# DC-DC_Controller.net
KiCad netlist of a schematic drawn in Altium Designer
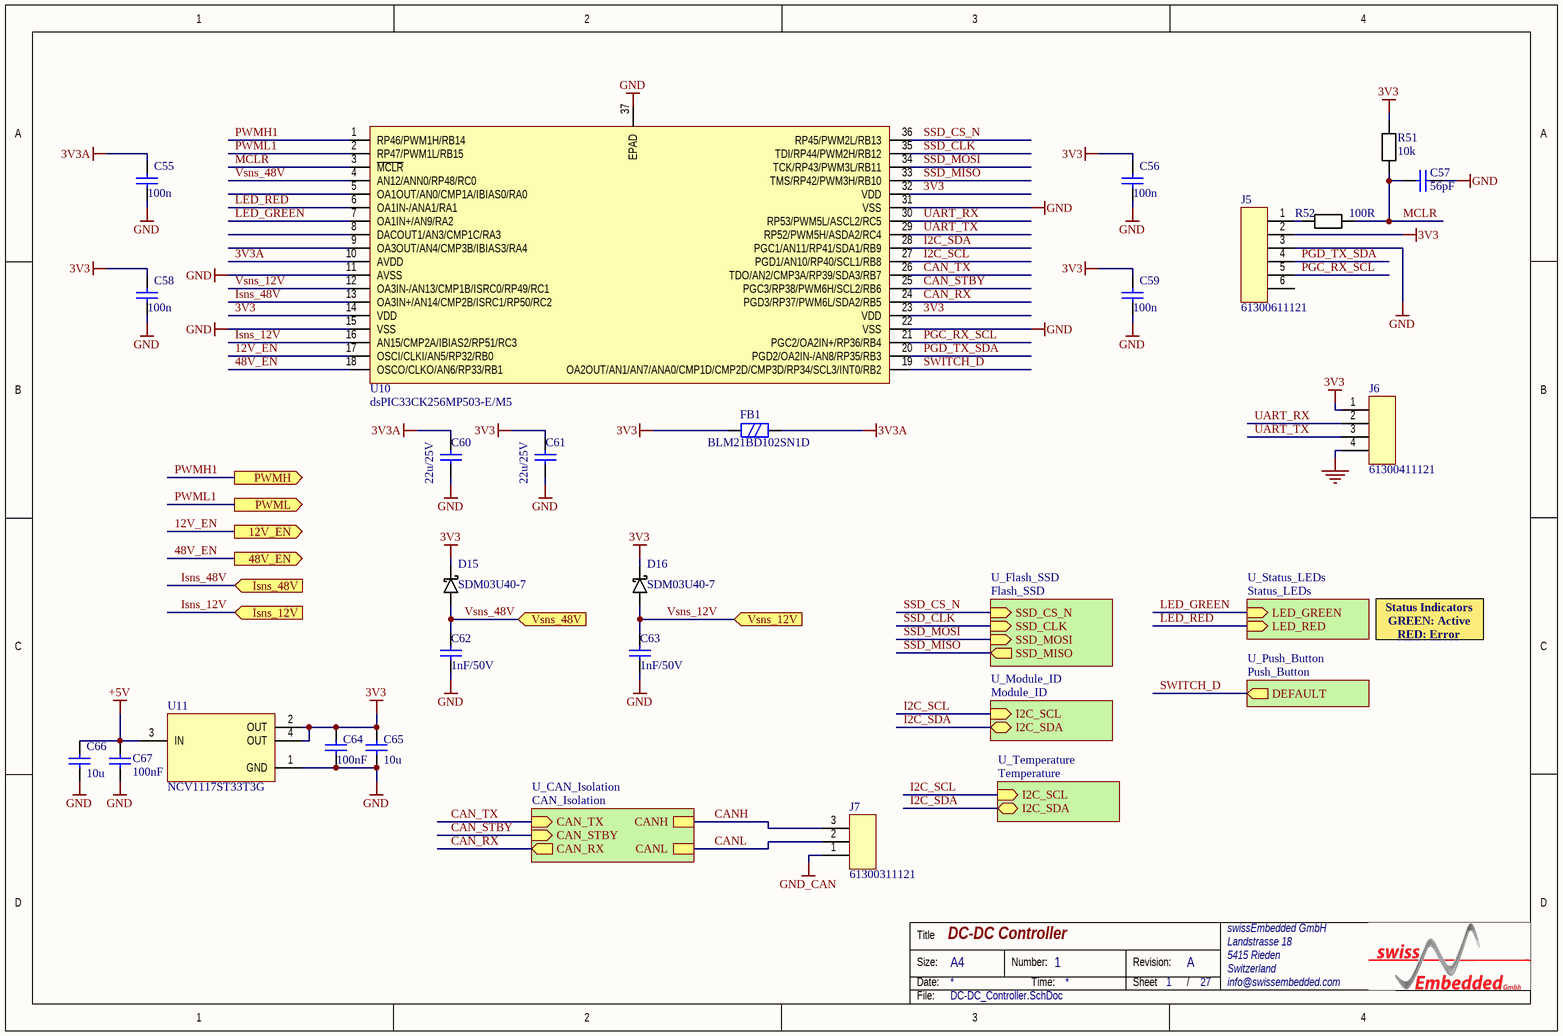
[diagram p0: DC-DC_Controller.SchDoc]

(export (version "E")
  (design (tool "Eeschema 10.0.6"))
  (components
    (comp (ref "C55")
      (value "100n")
      (footprint "C0603")
      (description "100nF ±10% 50V")
      (fields
        (field (name "PART NUMBER") "CAP_YAG_CC0603KRX7R9BB104_X7R")
        (field (name "MANUFACTURER") "Yageo")
      )
      (libsource (lib "Cap_Yag_0603_X7R_50_10%$") (part "CAP_YAG_CC0603KRX7R9BB104_X7R"))
    )
    (comp (ref "C56")
      (value "100n")
      (footprint "C0603")
      (description "100nF ±10% 50V")
      (fields
        (field (name "PART NUMBER") "CAP_YAG_CC0603KRX7R9BB104_X7R")
        (field (name "MANUFACTURER") "Yageo")
      )
      (libsource (lib "Cap_Yag_0603_X7R_50_10%$") (part "CAP_YAG_CC0603KRX7R9BB104_X7R"))
    )
    (comp (ref "C57")
      (value "56pF")
      (footprint "C0603")
      (description "330pF ± 5% 50V")
      (fields
        (field (name "MANUFACTURER") "Yageo")
        (field (name "MANUFACTURER PART NUMBER") "CC0603JRNPO9BN560")
      )
      (libsource (lib "RCL") (part "CAP"))
    )
    (comp (ref "C58")
      (value "100n")
      (footprint "C0603")
      (description "100nF ±10% 50V")
      (fields
        (field (name "PART NUMBER") "CAP_YAG_CC0603KRX7R9BB104_X7R")
        (field (name "MANUFACTURER") "Yageo")
      )
      (libsource (lib "Cap_Yag_0603_X7R_50_10%$") (part "CAP_YAG_CC0603KRX7R9BB104_X7R"))
    )
    (comp (ref "C59")
      (value "100n")
      (footprint "C0603")
      (description "100nF ±10% 50V")
      (fields
        (field (name "PART NUMBER") "CAP_YAG_CC0603KRX7R9BB104_X7R")
        (field (name "MANUFACTURER") "Yageo")
      )
      (libsource (lib "Cap_Yag_0603_X7R_50_10%$") (part "CAP_YAG_CC0603KRX7R9BB104_X7R"))
    )
    (comp (ref "C60")
      (value "22u/25V")
      (footprint "C0805")
      (description "22uF ±10% 25V")
      (fields
        (field (name "MANUFACTURER") "Yageo")
        (field (name "MANUFACTURER PART NUMBER") "CC0805MKX5R8BB226")
      )
      (libsource (lib "RCL") (part "CAP"))
    )
    (comp (ref "C61")
      (value "22u/25V")
      (footprint "C0805")
      (description "22uF ±10% 25V")
      (fields
        (field (name "MANUFACTURER") "Yageo")
        (field (name "MANUFACTURER PART NUMBER") "CC0805MKX5R8BB226")
      )
      (libsource (lib "RCL") (part "CAP"))
    )
    (comp (ref "C62")
      (value "1nF/50V")
      (footprint "C0603")
      (description "1nF ±10% 50V")
      (fields
        (field (name "MANUFACTURER") "Yageo")
        (field (name "MANUFACTURER PART NUMBER") "CC0603KRNPO9BN102")
      )
      (libsource (lib "RCL") (part "CAP"))
    )
    (comp (ref "C63")
      (value "1nF/50V")
      (footprint "C0603")
      (description "1nF ±10% 50V")
      (fields
        (field (name "MANUFACTURER") "Yageo")
        (field (name "MANUFACTURER PART NUMBER") "CC0603KRNPO9BN102")
      )
      (libsource (lib "RCL") (part "CAP"))
    )
    (comp (ref "C64")
      (value "100nF")
      (footprint "C0603")
      (description "100nF ± 10% 50V")
      (fields
        (field (name "MANUFACTURER") "Yageo")
        (field (name "MANUFACTURER PART NUMBER") "CC0603KRX7R9BB104")
      )
      (libsource (lib "Humidity Regulator") (part "100nF ± 10% 50V"))
    )
    (comp (ref "C65")
      (value "10u")
      (footprint "C1206")
      (description "10uF ± 10% 25V")
      (fields
        (field (name "MANUFACTURER") "Yageo")
        (field (name "MANUFACTURER PART NUMBER") "CC1206KKX7R8BB106")
      )
      (libsource (lib "Humidity Regulator") (part "10uF ± 10% 25V"))
    )
    (comp (ref "C66")
      (value "10u")
      (footprint "C1206")
      (description "10uF ± 10% 25V")
      (fields
        (field (name "MANUFACTURER") "Yageo")
        (field (name "MANUFACTURER PART NUMBER") "CC1206KKX7R8BB106")
      )
      (libsource (lib "Humidity Regulator") (part "10uF ± 10% 25V"))
    )
    (comp (ref "C67")
      (value "100nF")
      (footprint "C0603")
      (description "100nF ± 10% 50V")
      (fields
        (field (name "MANUFACTURER") "Yageo")
        (field (name "MANUFACTURER PART NUMBER") "CC0603KRX7R9BB104")
      )
      (libsource (lib "Humidity Regulator") (part "100nF ± 10% 50V"))
    )
    (comp (ref "D15")
      (value "SDM03U40-7")
      (footprint "SOD523")
      (description "Schottky Diodes & Rectifiers 40V 150mW")
      (fields (field (name "MANUFACTURER") "Diodes Incorporated"))
      (libsource (lib "EMDO601_Patch") (part "SDM03U40-7"))
    )
    (comp (ref "D16")
      (value "SDM03U40-7")
      (footprint "SOD523")
      (description "Schottky Diodes & Rectifiers 40V 150mW")
      (fields (field (name "MANUFACTURER") "Diodes Incorporated"))
      (libsource (lib "EMDO601_Patch") (part "SDM03U40-7"))
    )
    (comp (ref "FB1")
      (value "BLM21BD102SN1D")
      (footprint "R0805")
      (description "FERRITE BEAD 1 KOHM 0805 1LN")
      (fields (field (name "MANUFACTURER") "Murata Electronics"))
      (libsource (lib "SchematicLib") (part "SMD_FB"))
    )
    (comp (ref "J5")
      (value "61300611121")
      (footprint "Header-2.54m-6pin")
      (description "6 Pins 2.54mm Pitch Male Connector")
      (fields (field (name "MANUFACTURER") "Wurth Elektronik"))
      (libsource (lib "WirelessCharger") (part "6PinConnector"))
    )
    (comp (ref "J6")
      (value "61300411121")
      (footprint "Header-2.54m-4pin")
      (description "Headers & Wire Housings WR-PHD 2.54mm Hdr 4P Single Str Gold")
      (fields (field (name "MANUFACTURER") "Wurth"))
      (libsource (lib "EMDO601_Patch") (part "61300411121"))
    )
    (comp (ref "J7")
      (value "61300311121")
      (footprint "Header-2.54m-3pin")
      (description "Headers & Wire Housings WR-PHD 2.54mm Hdr 3P Single Str Gold")
      (fields (field (name "MANUFACTURER") "Wurth"))
      (libsource (lib "EMDO601_Patch") (part "61300311121"))
    )
    (comp (ref "R51")
      (value "10k")
      (footprint "R0603")
      (description "0.1W/ 10kohm±1%")
      (fields
        (field (name "MANUFACTURER PART NUMBER") "RC0603FR-0710KL")
        (field (name "MANUFACTURER") "Yageo")
      )
      (libsource (lib "RCL") (part "RES"))
    )
    (comp (ref "R52")
      (value "100R")
      (footprint "R0603")
      (description "0.1W/ 100 ohm±1%")
      (fields
        (field (name "MANUFACTURER PART NUMBER") "RC0603FR-07100RL")
        (field (name "MANUFACTURER") "Yageo")
      )
      (libsource (lib "RCL") (part "RES"))
    )
    (comp (ref "U10")
      (value "dsPIC33CK256MP503-E/M5")
      (footprint "UQFN-36")
      (fields
        (field (name "MANUFACTURER") "Microchip Technology")
        (field (name "ALTERNATIVE PART NUMBER") "dsPIC33CK128MP203-I/M5")
      )
      (libsource (lib "EMDO601_Patch") (part "dsPIC33CK256MP503-E/M5"))
    )
    (comp (ref "U11")
      (value "NCV1117ST33T3G")
      (footprint "SOT223-3")
      (description "LDO Voltage Regulators 3.3V 1.0A Automotive")
      (fields (field (name "MANUFACTURER") "onsemi"))
      (libsource (lib "Humidity Regulator") (part "NCV1117ST33T3G"))
    )
  )
  (nets
    (net (code "1") (name "+5V") (class "Default")
      (node (ref "C66") (pin "2") (pinfunction "2_2") (pintype "passive"))
      (node (ref "C67") (pin "2") (pinfunction "2_2") (pintype "passive"))
      (node (ref "U11") (pin "3") (pinfunction "IN_3") (pintype "power_in"))
    )
    (net (code "2") (name "/12V_EN") (class "Default")
      (node (ref "U10") (pin "17") (pinfunction "OSCI/CLKI/AN5/RP32/RB0_17") (pintype "passive"))
    )
    (net (code "3") (name "/48V_EN") (class "Default")
      (node (ref "U10") (pin "18") (pinfunction "OSCO/CLKO/AN6/RP33/RB1_18") (pintype "passive"))
    )
    (net (code "4") (name "/CANH") (class "Default")
      (node (ref "J7") (pin "3") (pinfunction "3_3") (pintype "passive"))
    )
    (net (code "5") (name "/CANL") (class "Default")
      (node (ref "J7") (pin "2") (pinfunction "2_2") (pintype "passive"))
    )
    (net (code "6") (name "/CAN_RX") (class "Default")
      (node (ref "U10") (pin "24") (pinfunction "PGD3/RP37/PWM6L/SDA2/RB5_24") (pintype "passive"))
    )
    (net (code "7") (name "/CAN_STBY") (class "Default")
      (node (ref "U10") (pin "25") (pinfunction "PGC3/RP38/PWM6H/SCL2/RB6_25") (pintype "passive"))
    )
    (net (code "8") (name "/CAN_TX") (class "Default")
      (node (ref "U10") (pin "26") (pinfunction "TDO/AN2/CMP3A/RP39/SDA3/RB7_26") (pintype "passive"))
    )
    (net (code "9") (name "/I2C_SCL") (class "Default")
      (node (ref "U10") (pin "27") (pinfunction "PGD1/AN10/RP40/SCL1/RB8_27") (pintype "passive"))
    )
    (net (code "10") (name "/I2C_SDA") (class "Default")
      (node (ref "U10") (pin "28") (pinfunction "PGC1/AN11/RP41/SDA1/RB9_28") (pintype "passive"))
    )
    (net (code "11") (name "/Isns_12V") (class "Default")
      (node (ref "U10") (pin "16") (pinfunction "AN15/CMP2A/IBIAS2/RP51/RC3_16") (pintype "passive"))
    )
    (net (code "12") (name "/Isns_48V") (class "Default")
      (node (ref "U10") (pin "13") (pinfunction "OA3IN+/AN14/CMP2B/ISRC1/RP50/RC2_13") (pintype "passive"))
    )
    (net (code "13") (name "/LED_GREEN") (class "Default")
      (node (ref "U10") (pin "7") (pinfunction "OA1IN+/AN9/RA2_7") (pintype "passive"))
    )
    (net (code "14") (name "/LED_RED") (class "Default")
      (node (ref "U10") (pin "6") (pinfunction "OA1IN-/ANA1/RA1_6") (pintype "passive"))
    )
    (net (code "15") (name "/MCLR") (class "Default")
      (node (ref "C57") (pin "1") (pinfunction "1_1") (pintype "passive"))
      (node (ref "R51") (pin "2") (pinfunction "2_2") (pintype "passive"))
      (node (ref "R52") (pin "2") (pinfunction "2_2") (pintype "passive"))
      (node (ref "U10") (pin "3") (pinfunction "~{MCLR}_3") (pintype "passive"))
    )
    (net (code "16") (name "/PGC_RX_SCL") (class "Default")
      (node (ref "J5") (pin "5") (pinfunction "5_5") (pintype "passive"))
      (node (ref "U10") (pin "21") (pinfunction "PGC2/OA2IN+/RP36/RB4_21") (pintype "passive"))
    )
    (net (code "17") (name "/PGD_TX_SDA") (class "Default")
      (node (ref "J5") (pin "4") (pinfunction "4_4") (pintype "passive"))
      (node (ref "U10") (pin "20") (pinfunction "PGD2/OA2IN-/AN8/RP35/RB3_20") (pintype "passive"))
    )
    (net (code "18") (name "/PWMH1") (class "Default")
      (node (ref "U10") (pin "1") (pinfunction "RP46/PWM1H/RB14_1") (pintype "passive"))
    )
    (net (code "19") (name "/PWML1") (class "Default")
      (node (ref "U10") (pin "2") (pinfunction "RP47/PWM1L/RB15_2") (pintype "passive"))
    )
    (net (code "20") (name "/SSD_CLK") (class "Default")
      (node (ref "U10") (pin "35") (pinfunction "TDI/RP44/PWM2H/RB12_35") (pintype "passive"))
    )
    (net (code "21") (name "/SSD_CS_N") (class "Default")
      (node (ref "U10") (pin "36") (pinfunction "RP45/PWM2L/RB13_36") (pintype "passive"))
    )
    (net (code "22") (name "/SSD_MISO") (class "Default")
      (node (ref "U10") (pin "33") (pinfunction "TMS/RP42/PWM3H/RB10_33") (pintype "passive"))
    )
    (net (code "23") (name "/SSD_MOSI") (class "Default")
      (node (ref "U10") (pin "34") (pinfunction "TCK/RP43/PWM3L/RB11_34") (pintype "passive"))
    )
    (net (code "24") (name "/SWITCH_D") (class "Default")
      (node (ref "U10") (pin "19") (pinfunction "OA2OUT/AN1/AN7/ANA0/CMP1D/CMP2D/CMP3D/RP34/SCL3/INT0/RB2_19") (pintype "passive"))
    )
    (net (code "25") (name "/UART_RX") (class "Default")
      (node (ref "J6") (pin "2") (pinfunction "2_2") (pintype "passive"))
      (node (ref "U10") (pin "30") (pinfunction "RP53/PWM5L/ASCL2/RC5_30") (pintype "passive"))
    )
    (net (code "26") (name "/UART_TX") (class "Default")
      (node (ref "J6") (pin "3") (pinfunction "3_3") (pintype "passive"))
      (node (ref "U10") (pin "29") (pinfunction "RP52/PWM5H/ASDA2/RC4_29") (pintype "passive"))
    )
    (net (code "27") (name "/Vsns_12V") (class "Default")
      (node (ref "C63") (pin "2") (pinfunction "2_2") (pintype "passive"))
      (node (ref "D16") (pin "A") (pinfunction "A_A") (pintype "passive"))
      (node (ref "U10") (pin "12") (pinfunction "OA3IN-/AN13/CMP1B/ISRC0/RP49/RC1_12") (pintype "passive"))
    )
    (net (code "28") (name "/Vsns_48V") (class "Default")
      (node (ref "C62") (pin "2") (pinfunction "2_2") (pintype "passive"))
      (node (ref "D15") (pin "A") (pinfunction "A_A") (pintype "passive"))
      (node (ref "U10") (pin "4") (pinfunction "AN12/ANN0/RP48/RC0_4") (pintype "passive"))
    )
    (net (code "29") (name "3V3") (class "Default")
      (node (ref "C56") (pin "2") (pinfunction "2_2") (pintype "passive"))
      (node (ref "C58") (pin "2") (pinfunction "2_2") (pintype "passive"))
      (node (ref "C59") (pin "2") (pinfunction "2_2") (pintype "passive"))
      (node (ref "C61") (pin "2") (pinfunction "2_2") (pintype "passive"))
      (node (ref "C64") (pin "2") (pinfunction "2_2") (pintype "passive"))
      (node (ref "C65") (pin "2") (pinfunction "2_2") (pintype "passive"))
      (node (ref "D15") (pin "C") (pinfunction "C_C") (pintype "passive"))
      (node (ref "D16") (pin "C") (pinfunction "C_C") (pintype "passive"))
      (node (ref "FB1") (pin "2") (pinfunction "2_2") (pintype "passive"))
      (node (ref "J5") (pin "2") (pinfunction "2_2") (pintype "passive"))
      (node (ref "J6") (pin "1") (pinfunction "1_1") (pintype "passive"))
      (node (ref "R51") (pin "1") (pinfunction "1_1") (pintype "passive"))
      (node (ref "U10") (pin "14") (pinfunction "VDD_14") (pintype "passive"))
      (node (ref "U10") (pin "23") (pinfunction "VDD_23") (pintype "passive"))
      (node (ref "U10") (pin "32") (pinfunction "VDD_32") (pintype "passive"))
      (node (ref "U11") (pin "2") (pinfunction "OUT_2") (pintype "power_in"))
      (node (ref "U11") (pin "4") (pinfunction "OUT_4") (pintype "power_in"))
    )
    (net (code "30") (name "3V3A") (class "Default")
      (node (ref "C55") (pin "2") (pinfunction "2_2") (pintype "passive"))
      (node (ref "C60") (pin "2") (pinfunction "2_2") (pintype "passive"))
      (node (ref "FB1") (pin "1") (pinfunction "1_1") (pintype "passive"))
      (node (ref "U10") (pin "10") (pinfunction "AVDD_10") (pintype "passive"))
    )
    (net (code "31") (name "GND") (class "Default")
      (node (ref "C55") (pin "1") (pinfunction "1_1") (pintype "passive"))
      (node (ref "C56") (pin "1") (pinfunction "1_1") (pintype "passive"))
      (node (ref "C57") (pin "2") (pinfunction "2_2") (pintype "passive"))
      (node (ref "C58") (pin "1") (pinfunction "1_1") (pintype "passive"))
      (node (ref "C59") (pin "1") (pinfunction "1_1") (pintype "passive"))
      (node (ref "C60") (pin "1") (pinfunction "1_1") (pintype "passive"))
      (node (ref "C61") (pin "1") (pinfunction "1_1") (pintype "passive"))
      (node (ref "C62") (pin "1") (pinfunction "1_1") (pintype "passive"))
      (node (ref "C63") (pin "1") (pinfunction "1_1") (pintype "passive"))
      (node (ref "C64") (pin "1") (pinfunction "1_1") (pintype "passive"))
      (node (ref "C65") (pin "1") (pinfunction "1_1") (pintype "passive"))
      (node (ref "C66") (pin "1") (pinfunction "1_1") (pintype "passive"))
      (node (ref "C67") (pin "1") (pinfunction "1_1") (pintype "passive"))
      (node (ref "J5") (pin "3") (pinfunction "3_3") (pintype "passive"))
      (node (ref "J6") (pin "4") (pinfunction "4_4") (pintype "passive"))
      (node (ref "U10") (pin "11") (pinfunction "AVSS_11") (pintype "passive"))
      (node (ref "U10") (pin "15") (pinfunction "VSS_15") (pintype "passive"))
      (node (ref "U10") (pin "22") (pinfunction "VSS_22") (pintype "passive"))
      (node (ref "U10") (pin "31") (pinfunction "VSS_31") (pintype "passive"))
      (node (ref "U10") (pin "37") (pinfunction "EPAD_37") (pintype "passive"))
      (node (ref "U11") (pin "1") (pinfunction "GND_1") (pintype "power_in"))
    )
    (net (code "32") (name "GND_CAN") (class "Default")
      (node (ref "J7") (pin "1") (pinfunction "1_1") (pintype "passive"))
    )
    (net (code "33") (name "Net-(J5-Pad1)") (class "Default")
      (node (ref "J5") (pin "1") (pinfunction "1_1") (pintype "passive"))
      (node (ref "R52") (pin "1") (pinfunction "1_1") (pintype "passive"))
    )
    (net (code "34") (name "unconnected-(J5-Pad6)") (class "Default")
      (node (ref "J5") (pin "6") (pinfunction "6_6") (pintype "passive"))
    )
    (net (code "35") (name "unconnected-(U10-DACOUT1{slash}AN3{slash}CMP1C{slash}RA3-Pad8)") (class "Default")
      (node (ref "U10") (pin "8") (pinfunction "DACOUT1/AN3/CMP1C/RA3_8") (pintype "passive"))
    )
    (net (code "36") (name "unconnected-(U10-OA1OUT{slash}AN0{slash}CMP1A{slash}IBIAS0{slash}RA0-Pad5)") (class "Default")
      (node (ref "U10") (pin "5") (pinfunction "OA1OUT/AN0/CMP1A/IBIAS0/RA0_5") (pintype "passive"))
    )
    (net (code "37") (name "unconnected-(U10-OA3OUT{slash}AN4{slash}CMP3B{slash}IBIAS3{slash}RA4-Pad9)") (class "Default")
      (node (ref "U10") (pin "9") (pinfunction "OA3OUT/AN4/CMP3B/IBIAS3/RA4_9") (pintype "passive"))
    )
  )
)
